# ESD_Protection.net
KiCad netlist of a schematic drawn in Altium Designer
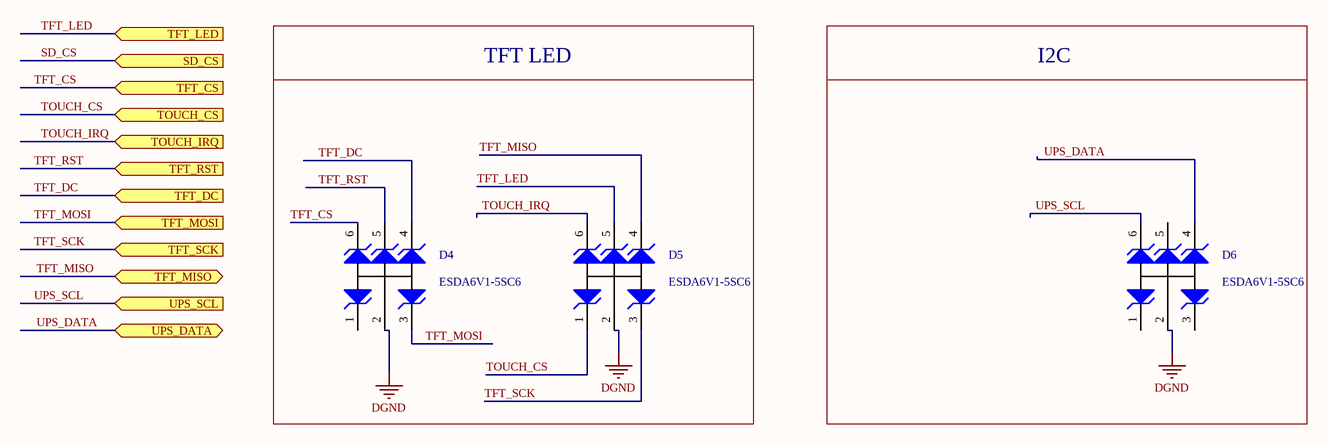
[diagram p0: ESD_Protection.SchDoc]

(export (version "E")
  (design (tool "Eeschema 10.0.6"))
  (components
    (comp (ref "D4")
      (value "ESDA6V1-5SC6")
      (footprint "MF06A_N")
      (description "ESDA Series 5 Channel 6.1 V 50 pF SMT Uni Directional Transil Array - SOT-23-6L")
      (libsource (lib "CommunityVault") (part "CMP-924f5b40f9684d88-1"))
    )
    (comp (ref "D5")
      (value "ESDA6V1-5SC6")
      (footprint "MF06A_N")
      (description "ESDA Series 5 Channel 6.1 V 50 pF SMT Uni Directional Transil Array - SOT-23-6L")
      (libsource (lib "CommunityVault") (part "CMP-924f5b40f9684d88-1"))
    )
    (comp (ref "D6")
      (value "ESDA6V1-5SC6")
      (footprint "MF06A_N")
      (description "ESDA Series 5 Channel 6.1 V 50 pF SMT Uni Directional Transil Array - SOT-23-6L")
      (libsource (lib "CommunityVault") (part "CMP-924f5b40f9684d88-1"))
    )
  )
  (nets
    (net (code "2") (name "/TFT_CS") (class "Default")
      (node (ref "D4") (pin "6") (pinfunction "A_6") (pintype "passive"))
    )
    (net (code "3") (name "/TFT_DC") (class "Default")
      (node (ref "D4") (pin "4") (pinfunction "A_4") (pintype "passive"))
    )
    (net (code "4") (name "/TFT_LED") (class "Default")
      (node (ref "D5") (pin "5") (pinfunction "A_5") (pintype "passive"))
    )
    (net (code "5") (name "/TFT_MISO") (class "Default")
      (node (ref "D5") (pin "4") (pinfunction "A_4") (pintype "passive"))
    )
    (net (code "6") (name "/TFT_MOSI") (class "Default")
      (node (ref "D4") (pin "3") (pinfunction "K_3") (pintype "passive"))
    )
    (net (code "7") (name "/TFT_RST") (class "Default")
      (node (ref "D4") (pin "5") (pinfunction "A_5") (pintype "passive"))
    )
    (net (code "8") (name "/TFT_SCK") (class "Default")
      (node (ref "D5") (pin "3") (pinfunction "K_3") (pintype "passive"))
    )
    (net (code "9") (name "/TOUCH_CS") (class "Default")
      (node (ref "D5") (pin "1") (pinfunction "K_1") (pintype "passive"))
    )
    (net (code "10") (name "/TOUCH_IRQ") (class "Default")
      (node (ref "D5") (pin "6") (pinfunction "A_6") (pintype "passive"))
    )
    (net (code "11") (name "/UPS_DATA") (class "Default")
      (node (ref "D6") (pin "4") (pinfunction "A_4") (pintype "passive"))
    )
    (net (code "12") (name "/UPS_SCL") (class "Default")
      (node (ref "D6") (pin "6") (pinfunction "A_6") (pintype "passive"))
    )
    (net (code "13") (name "DGND") (class "Default")
      (node (ref "D4") (pin "2") (pinfunction "K_2") (pintype "passive"))
      (node (ref "D5") (pin "2") (pinfunction "K_2") (pintype "passive"))
      (node (ref "D6") (pin "2") (pinfunction "K_2") (pintype "passive"))
    )
    (net (code "14") (name "unconnected-(D4-K-Pad1)") (class "Default")
      (node (ref "D4") (pin "1") (pinfunction "K_1") (pintype "passive"))
    )
    (net (code "15") (name "unconnected-(D6-A-Pad5)") (class "Default")
      (node (ref "D6") (pin "5") (pinfunction "A_5") (pintype "passive"))
    )
    (net (code "16") (name "unconnected-(D6-K-Pad1)") (class "Default")
      (node (ref "D6") (pin "1") (pinfunction "K_1") (pintype "passive"))
    )
    (net (code "17") (name "unconnected-(D6-K-Pad3)") (class "Default")
      (node (ref "D6") (pin "3") (pinfunction "K_3") (pintype "passive"))
    )
  )
)
